# Schematic.net
KiCad netlist of a schematic drawn in Altium Designer
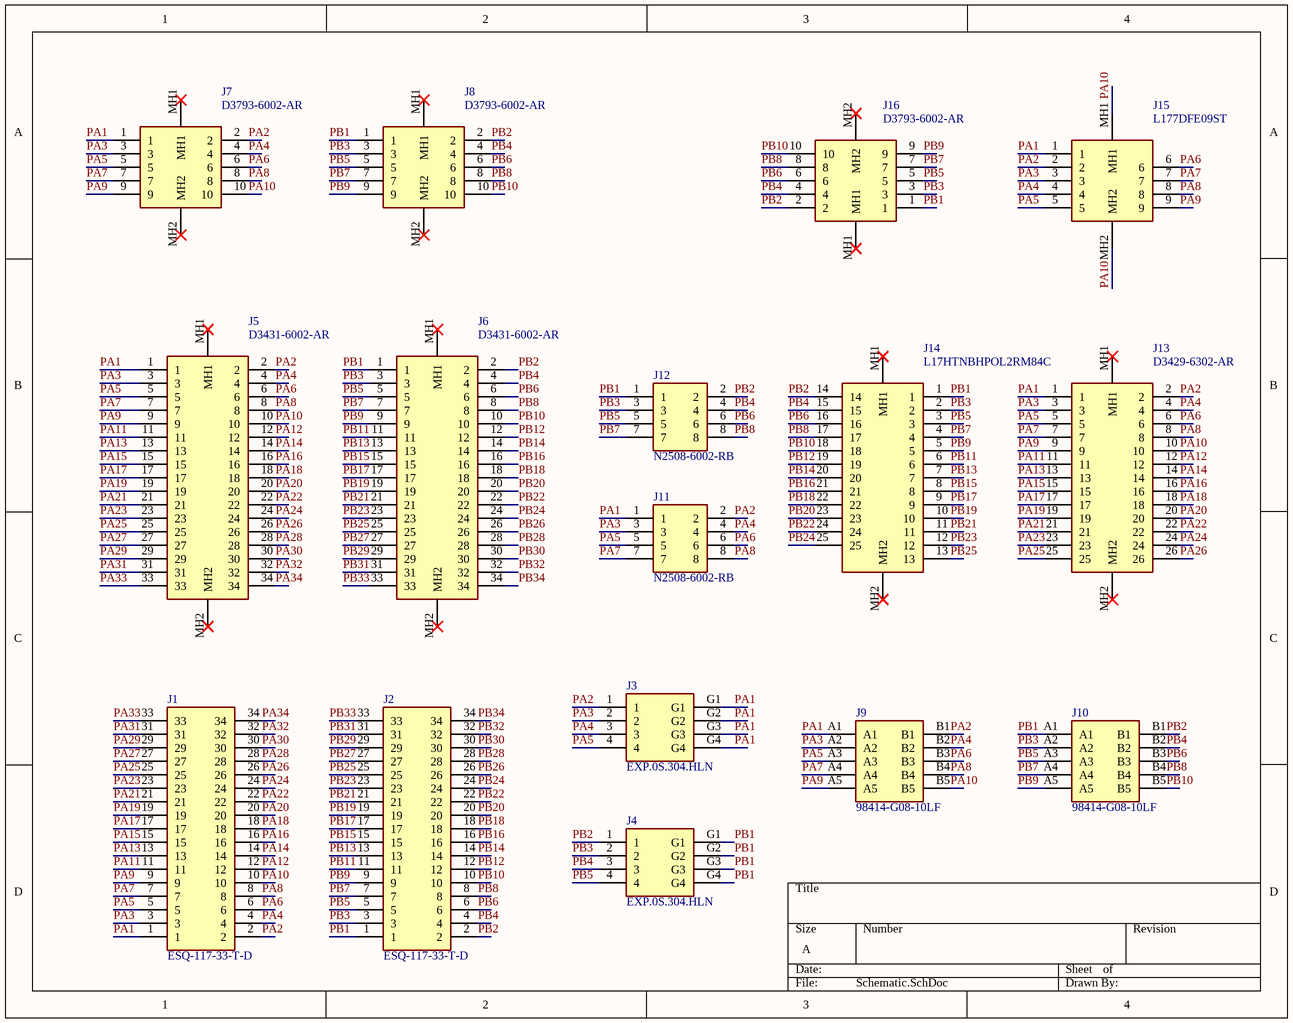
[diagram p0: Schematic.SchDoc]

(export (version "E")
  (design (tool "Eeschema 10.0.6"))
  (components
    (comp (ref "J1")
      (value "ESQ-117-33-T-D")
      (footprint "ESQ-117-Y-X-D")
      (description "Connector")
      (fields
        (field (name "MANUFACTURER_PART_NUMBER") "ESQ-117-44-T-D")
        (field (name "MOUSER PART NUMBER") "200-ESQ11744TD")
      )
      (libsource (lib "Connectors") (part "ESQ-117-33-T-D"))
    )
    (comp (ref "J2")
      (value "ESQ-117-33-T-D")
      (footprint "ESQ-117-Y-X-D")
      (description "Connector")
      (fields
        (field (name "MANUFACTURER_PART_NUMBER") "ESQ-117-44-T-D")
        (field (name "MOUSER PART NUMBER") "200-ESQ11744TD")
      )
      (libsource (lib "Connectors") (part "ESQ-117-33-T-D"))
    )
    (comp (ref "J3")
      (value "EXP.0S.304.HLN")
      (footprint "EXP0S304HLN")
      (description "Connector")
      (fields (field (name "MOUSER PART NUMBER") "736-EXP0S304HLN"))
      (libsource (lib "Connectors") (part "EXP.0S.304.HLN"))
    )
    (comp (ref "J4")
      (value "EXP.0S.304.HLN")
      (footprint "EXP0S304HLN")
      (description "Connector")
      (fields (field (name "MOUSER PART NUMBER") "736-EXP0S304HLN"))
      (libsource (lib "Connectors") (part "EXP.0S.304.HLN"))
    )
    (comp (ref "J5")
      (value "D3431-6002-AR")
      (footprint "D3431-6002-AR")
      (description "Connector")
      (libsource (lib "Connectors") (part "D3431-6002-AR"))
    )
    (comp (ref "J6")
      (value "D3431-6002-AR")
      (footprint "D3431-6002-AR")
      (description "Connector")
      (libsource (lib "Connectors") (part "D3431-6002-AR"))
    )
    (comp (ref "J7")
      (value "D3793-6002-AR")
      (footprint "D3793-6002-AR")
      (description "Connector")
      (libsource (lib "Connectors") (part "D3793-6002-AR"))
    )
    (comp (ref "J8")
      (value "D3793-6002-AR")
      (footprint "D3793-6002-AR")
      (description "Connector")
      (libsource (lib "Connectors") (part "D3793-6002-AR"))
    )
    (comp (ref "J9")
      (value "98414-G08-10LF")
      (footprint "98414G0810LF")
      (description "Connector")
      (fields (field (name "MOUSER PART NUMBER") "649-98414-G08-10LF"))
      (libsource (lib "Connectors") (part "98414-G08-10LF"))
    )
    (comp (ref "J10")
      (value "98414-G08-10LF")
      (footprint "98414G0810LF")
      (description "Connector")
      (fields (field (name "MOUSER PART NUMBER") "649-98414-G08-10LF"))
      (libsource (lib "Connectors") (part "98414-G08-10LF"))
    )
    (comp (ref "J11")
      (value "N2508-6002-RB")
      (footprint "SHDR8W64P254_2X4_1748X859X1004P")
      (description "Connector")
      (fields (field (name "MOUSER PART NUMBER") "517-N2508-6002-RB"))
      (libsource (lib "Connectors") (part "N2508-6002-RB"))
    )
    (comp (ref "J12")
      (value "N2508-6002-RB")
      (footprint "SHDR8W64P254_2X4_1748X859X1004P")
      (description "Connector")
      (fields (field (name "MOUSER PART NUMBER") "517-N2508-6002-RB"))
      (libsource (lib "Connectors") (part "N2508-6002-RB"))
    )
    (comp (ref "J13")
      (value "D3429-6302-AR")
      (footprint "D34296302AR")
      (description "Connector")
      (fields (field (name "MOUSER PART NUMBER") "517-D3429-6302-AR"))
      (libsource (lib "Connectors") (part "D3429-6302-AR"))
    )
    (comp (ref "J14")
      (value "L17HTNBHPOL2RM84C")
      (footprint "L17HTNBHPOL2RM84C")
      (description "Connector")
      (fields (field (name "MOUSER PART NUMBER") "523-17HTNBHPOL2RM84C"))
      (libsource (lib "Connectors") (part "L17HTNBHPOL2RM84C"))
    )
    (comp (ref "J15")
      (value "L177DFE09ST")
      (footprint "L177DFE09ST")
      (description "Connector")
      (libsource (lib "Connectors") (part "L177DFE09ST"))
    )
    (comp (ref "J16")
      (value "D3793-6002-AR")
      (footprint "D3793-6002-AR")
      (description "Connector")
      (libsource (lib "") (part "D3793-6002-AR_1"))
    )
  )
  (nets
    (net (code "1") (name "/PA1") (class "Default")
      (node (ref "J1") (pin "1") (pinfunction "1_1") (pintype "passive"))
      (node (ref "J11") (pin "1") (pinfunction "1_1") (pintype "passive"))
      (node (ref "J13") (pin "1") (pinfunction "1_1") (pintype "passive"))
      (node (ref "J15") (pin "1") (pinfunction "1_1") (pintype "passive"))
      (node (ref "J3") (pin "G1") (pinfunction "G1_G1") (pintype "passive"))
      (node (ref "J3") (pin "G2") (pinfunction "G2_G2") (pintype "passive"))
      (node (ref "J3") (pin "G3") (pinfunction "G3_G3") (pintype "passive"))
      (node (ref "J3") (pin "G4") (pinfunction "G4_G4") (pintype "passive"))
      (node (ref "J5") (pin "1") (pinfunction "1_1") (pintype "passive"))
      (node (ref "J7") (pin "1") (pinfunction "1_1") (pintype "passive"))
      (node (ref "J9") (pin "A1") (pinfunction "A1_A1") (pintype "passive"))
    )
    (net (code "2") (name "/PA2") (class "Default")
      (node (ref "J1") (pin "2") (pinfunction "2_2") (pintype "passive"))
      (node (ref "J11") (pin "2") (pinfunction "2_2") (pintype "passive"))
      (node (ref "J13") (pin "2") (pinfunction "2_2") (pintype "passive"))
      (node (ref "J15") (pin "2") (pinfunction "2_2") (pintype "passive"))
      (node (ref "J3") (pin "1") (pinfunction "1_1") (pintype "passive"))
      (node (ref "J5") (pin "2") (pinfunction "2_2") (pintype "passive"))
      (node (ref "J7") (pin "2") (pinfunction "2_2") (pintype "passive"))
      (node (ref "J9") (pin "B1") (pinfunction "B1_B1") (pintype "passive"))
    )
    (net (code "3") (name "/PA3") (class "Default")
      (node (ref "J1") (pin "3") (pinfunction "3_3") (pintype "passive"))
      (node (ref "J11") (pin "3") (pinfunction "3_3") (pintype "passive"))
      (node (ref "J13") (pin "3") (pinfunction "3_3") (pintype "passive"))
      (node (ref "J15") (pin "3") (pinfunction "3_3") (pintype "passive"))
      (node (ref "J3") (pin "2") (pinfunction "2_2") (pintype "passive"))
      (node (ref "J5") (pin "3") (pinfunction "3_3") (pintype "passive"))
      (node (ref "J7") (pin "3") (pinfunction "3_3") (pintype "passive"))
      (node (ref "J9") (pin "A2") (pinfunction "A2_A2") (pintype "passive"))
    )
    (net (code "4") (name "/PA4") (class "Default")
      (node (ref "J1") (pin "4") (pinfunction "4_4") (pintype "passive"))
      (node (ref "J11") (pin "4") (pinfunction "4_4") (pintype "passive"))
      (node (ref "J13") (pin "4") (pinfunction "4_4") (pintype "passive"))
      (node (ref "J15") (pin "4") (pinfunction "4_4") (pintype "passive"))
      (node (ref "J3") (pin "3") (pinfunction "3_3") (pintype "passive"))
      (node (ref "J5") (pin "4") (pinfunction "4_4") (pintype "passive"))
      (node (ref "J7") (pin "4") (pinfunction "4_4") (pintype "passive"))
      (node (ref "J9") (pin "B2") (pinfunction "B2_B2") (pintype "passive"))
    )
    (net (code "5") (name "/PA5") (class "Default")
      (node (ref "J1") (pin "5") (pinfunction "5_5") (pintype "passive"))
      (node (ref "J11") (pin "5") (pinfunction "5_5") (pintype "passive"))
      (node (ref "J13") (pin "5") (pinfunction "5_5") (pintype "passive"))
      (node (ref "J15") (pin "5") (pinfunction "5_5") (pintype "passive"))
      (node (ref "J3") (pin "4") (pinfunction "4_4") (pintype "passive"))
      (node (ref "J5") (pin "5") (pinfunction "5_5") (pintype "passive"))
      (node (ref "J7") (pin "5") (pinfunction "5_5") (pintype "passive"))
      (node (ref "J9") (pin "A3") (pinfunction "A3_A3") (pintype "passive"))
    )
    (net (code "6") (name "/PA6") (class "Default")
      (node (ref "J1") (pin "6") (pinfunction "6_6") (pintype "passive"))
      (node (ref "J11") (pin "6") (pinfunction "6_6") (pintype "passive"))
      (node (ref "J13") (pin "6") (pinfunction "6_6") (pintype "passive"))
      (node (ref "J15") (pin "6") (pinfunction "6_6") (pintype "passive"))
      (node (ref "J5") (pin "6") (pinfunction "6_6") (pintype "passive"))
      (node (ref "J7") (pin "6") (pinfunction "6_6") (pintype "passive"))
      (node (ref "J9") (pin "B3") (pinfunction "B3_B3") (pintype "passive"))
    )
    (net (code "7") (name "/PA7") (class "Default")
      (node (ref "J1") (pin "7") (pinfunction "7_7") (pintype "passive"))
      (node (ref "J11") (pin "7") (pinfunction "7_7") (pintype "passive"))
      (node (ref "J13") (pin "7") (pinfunction "7_7") (pintype "passive"))
      (node (ref "J15") (pin "7") (pinfunction "7_7") (pintype "passive"))
      (node (ref "J5") (pin "7") (pinfunction "7_7") (pintype "passive"))
      (node (ref "J7") (pin "7") (pinfunction "7_7") (pintype "passive"))
      (node (ref "J9") (pin "A4") (pinfunction "A4_A4") (pintype "passive"))
    )
    (net (code "8") (name "/PA8") (class "Default")
      (node (ref "J1") (pin "8") (pinfunction "8_8") (pintype "passive"))
      (node (ref "J11") (pin "8") (pinfunction "8_8") (pintype "passive"))
      (node (ref "J13") (pin "8") (pinfunction "8_8") (pintype "passive"))
      (node (ref "J15") (pin "8") (pinfunction "8_8") (pintype "passive"))
      (node (ref "J5") (pin "8") (pinfunction "8_8") (pintype "passive"))
      (node (ref "J7") (pin "8") (pinfunction "8_8") (pintype "passive"))
      (node (ref "J9") (pin "B4") (pinfunction "B4_B4") (pintype "passive"))
    )
    (net (code "9") (name "/PA9") (class "Default")
      (node (ref "J1") (pin "9") (pinfunction "9_9") (pintype "passive"))
      (node (ref "J13") (pin "9") (pinfunction "9_9") (pintype "passive"))
      (node (ref "J15") (pin "9") (pinfunction "9_9") (pintype "passive"))
      (node (ref "J5") (pin "9") (pinfunction "9_9") (pintype "passive"))
      (node (ref "J7") (pin "9") (pinfunction "9_9") (pintype "passive"))
      (node (ref "J9") (pin "A5") (pinfunction "A5_A5") (pintype "passive"))
    )
    (net (code "10") (name "/PA10") (class "Default")
      (node (ref "J1") (pin "10") (pinfunction "10_10") (pintype "passive"))
      (node (ref "J13") (pin "10") (pinfunction "10_10") (pintype "passive"))
      (node (ref "J15") (pin "MH1") (pinfunction "MH1_MH1") (pintype "passive"))
      (node (ref "J15") (pin "MH2") (pinfunction "MH2_MH2") (pintype "passive"))
      (node (ref "J5") (pin "10") (pinfunction "10_10") (pintype "passive"))
      (node (ref "J7") (pin "10") (pinfunction "10_10") (pintype "passive"))
      (node (ref "J9") (pin "B5") (pinfunction "B5_B5") (pintype "passive"))
    )
    (net (code "11") (name "/PA11") (class "Default")
      (node (ref "J1") (pin "11") (pinfunction "11_11") (pintype "passive"))
      (node (ref "J13") (pin "11") (pinfunction "11_11") (pintype "passive"))
      (node (ref "J5") (pin "11") (pinfunction "11_11") (pintype "passive"))
    )
    (net (code "12") (name "/PA12") (class "Default")
      (node (ref "J1") (pin "12") (pinfunction "12_12") (pintype "passive"))
      (node (ref "J13") (pin "12") (pinfunction "12_12") (pintype "passive"))
      (node (ref "J5") (pin "12") (pinfunction "12_12") (pintype "passive"))
    )
    (net (code "13") (name "/PA13") (class "Default")
      (node (ref "J1") (pin "13") (pinfunction "13_13") (pintype "passive"))
      (node (ref "J13") (pin "13") (pinfunction "13_13") (pintype "passive"))
      (node (ref "J5") (pin "13") (pinfunction "13_13") (pintype "passive"))
    )
    (net (code "14") (name "/PA14") (class "Default")
      (node (ref "J1") (pin "14") (pinfunction "14_14") (pintype "passive"))
      (node (ref "J13") (pin "14") (pinfunction "14_14") (pintype "passive"))
      (node (ref "J5") (pin "14") (pinfunction "14_14") (pintype "passive"))
    )
    (net (code "15") (name "/PA15") (class "Default")
      (node (ref "J1") (pin "15") (pinfunction "15_15") (pintype "passive"))
      (node (ref "J13") (pin "15") (pinfunction "15_15") (pintype "passive"))
      (node (ref "J5") (pin "15") (pinfunction "15_15") (pintype "passive"))
    )
    (net (code "16") (name "/PA16") (class "Default")
      (node (ref "J1") (pin "16") (pinfunction "16_16") (pintype "passive"))
      (node (ref "J13") (pin "16") (pinfunction "16_16") (pintype "passive"))
      (node (ref "J5") (pin "16") (pinfunction "16_16") (pintype "passive"))
    )
    (net (code "17") (name "/PA17") (class "Default")
      (node (ref "J1") (pin "17") (pinfunction "17_17") (pintype "passive"))
      (node (ref "J13") (pin "17") (pinfunction "17_17") (pintype "passive"))
      (node (ref "J5") (pin "17") (pinfunction "17_17") (pintype "passive"))
    )
    (net (code "18") (name "/PA18") (class "Default")
      (node (ref "J1") (pin "18") (pinfunction "18_18") (pintype "passive"))
      (node (ref "J13") (pin "18") (pinfunction "18_18") (pintype "passive"))
      (node (ref "J5") (pin "18") (pinfunction "18_18") (pintype "passive"))
    )
    (net (code "19") (name "/PA19") (class "Default")
      (node (ref "J1") (pin "19") (pinfunction "19_19") (pintype "passive"))
      (node (ref "J13") (pin "19") (pinfunction "19_19") (pintype "passive"))
      (node (ref "J5") (pin "19") (pinfunction "19_19") (pintype "passive"))
    )
    (net (code "20") (name "/PA20") (class "Default")
      (node (ref "J1") (pin "20") (pinfunction "20_20") (pintype "passive"))
      (node (ref "J13") (pin "20") (pinfunction "20_20") (pintype "passive"))
      (node (ref "J5") (pin "20") (pinfunction "20_20") (pintype "passive"))
    )
    (net (code "21") (name "/PA21") (class "Default")
      (node (ref "J1") (pin "21") (pinfunction "21_21") (pintype "passive"))
      (node (ref "J13") (pin "21") (pinfunction "21_21") (pintype "passive"))
      (node (ref "J5") (pin "21") (pinfunction "21_21") (pintype "passive"))
    )
    (net (code "22") (name "/PA22") (class "Default")
      (node (ref "J1") (pin "22") (pinfunction "22_22") (pintype "passive"))
      (node (ref "J13") (pin "22") (pinfunction "22_22") (pintype "passive"))
      (node (ref "J5") (pin "22") (pinfunction "22_22") (pintype "passive"))
    )
    (net (code "23") (name "/PA23") (class "Default")
      (node (ref "J1") (pin "23") (pinfunction "23_23") (pintype "passive"))
      (node (ref "J13") (pin "23") (pinfunction "23_23") (pintype "passive"))
      (node (ref "J5") (pin "23") (pinfunction "23_23") (pintype "passive"))
    )
    (net (code "24") (name "/PA24") (class "Default")
      (node (ref "J1") (pin "24") (pinfunction "24_24") (pintype "passive"))
      (node (ref "J13") (pin "24") (pinfunction "24_24") (pintype "passive"))
      (node (ref "J5") (pin "24") (pinfunction "24_24") (pintype "passive"))
    )
    (net (code "25") (name "/PA25") (class "Default")
      (node (ref "J1") (pin "25") (pinfunction "25_25") (pintype "passive"))
      (node (ref "J13") (pin "25") (pinfunction "25_25") (pintype "passive"))
      (node (ref "J5") (pin "25") (pinfunction "25_25") (pintype "passive"))
    )
    (net (code "26") (name "/PA26") (class "Default")
      (node (ref "J1") (pin "26") (pinfunction "26_26") (pintype "passive"))
      (node (ref "J13") (pin "26") (pinfunction "26_26") (pintype "passive"))
      (node (ref "J5") (pin "26") (pinfunction "26_26") (pintype "passive"))
    )
    (net (code "27") (name "/PA27") (class "Default")
      (node (ref "J1") (pin "27") (pinfunction "27_27") (pintype "passive"))
      (node (ref "J5") (pin "27") (pinfunction "27_27") (pintype "passive"))
    )
    (net (code "28") (name "/PA28") (class "Default")
      (node (ref "J1") (pin "28") (pinfunction "28_28") (pintype "passive"))
      (node (ref "J5") (pin "28") (pinfunction "28_28") (pintype "passive"))
    )
    (net (code "29") (name "/PA29") (class "Default")
      (node (ref "J1") (pin "29") (pinfunction "29_29") (pintype "passive"))
      (node (ref "J5") (pin "29") (pinfunction "29_29") (pintype "passive"))
    )
    (net (code "30") (name "/PA30") (class "Default")
      (node (ref "J1") (pin "30") (pinfunction "30_30") (pintype "passive"))
      (node (ref "J5") (pin "30") (pinfunction "30_30") (pintype "passive"))
    )
    (net (code "31") (name "/PA31") (class "Default")
      (node (ref "J1") (pin "31") (pinfunction "31_31") (pintype "passive"))
      (node (ref "J5") (pin "31") (pinfunction "31_31") (pintype "passive"))
    )
    (net (code "32") (name "/PA32") (class "Default")
      (node (ref "J1") (pin "32") (pinfunction "32_32") (pintype "passive"))
      (node (ref "J5") (pin "32") (pinfunction "32_32") (pintype "passive"))
    )
    (net (code "33") (name "/PA33") (class "Default")
      (node (ref "J1") (pin "33") (pinfunction "33_33") (pintype "passive"))
      (node (ref "J5") (pin "33") (pinfunction "33_33") (pintype "passive"))
    )
    (net (code "34") (name "/PA34") (class "Default")
      (node (ref "J1") (pin "34") (pinfunction "34_34") (pintype "passive"))
      (node (ref "J5") (pin "34") (pinfunction "34_34") (pintype "passive"))
    )
    (net (code "35") (name "/PB1") (class "Default")
      (node (ref "J10") (pin "A1") (pinfunction "A1_A1") (pintype "passive"))
      (node (ref "J12") (pin "1") (pinfunction "1_1") (pintype "passive"))
      (node (ref "J14") (pin "1") (pinfunction "1_1") (pintype "passive"))
      (node (ref "J16") (pin "1") (pinfunction "1_1") (pintype "passive"))
      (node (ref "J2") (pin "1") (pinfunction "1_1") (pintype "passive"))
      (node (ref "J4") (pin "G1") (pinfunction "G1_G1") (pintype "passive"))
      (node (ref "J4") (pin "G2") (pinfunction "G2_G2") (pintype "passive"))
      (node (ref "J4") (pin "G3") (pinfunction "G3_G3") (pintype "passive"))
      (node (ref "J4") (pin "G4") (pinfunction "G4_G4") (pintype "passive"))
      (node (ref "J6") (pin "1") (pinfunction "1_1") (pintype "passive"))
      (node (ref "J8") (pin "1") (pinfunction "1_1") (pintype "passive"))
    )
    (net (code "36") (name "/PB2") (class "Default")
      (node (ref "J10") (pin "B1") (pinfunction "B1_B1") (pintype "passive"))
      (node (ref "J12") (pin "2") (pinfunction "2_2") (pintype "passive"))
      (node (ref "J14") (pin "14") (pinfunction "14_14") (pintype "passive"))
      (node (ref "J16") (pin "2") (pinfunction "2_2") (pintype "passive"))
      (node (ref "J2") (pin "2") (pinfunction "2_2") (pintype "passive"))
      (node (ref "J4") (pin "1") (pinfunction "1_1") (pintype "passive"))
      (node (ref "J6") (pin "2") (pinfunction "2_2") (pintype "passive"))
      (node (ref "J8") (pin "2") (pinfunction "2_2") (pintype "passive"))
    )
    (net (code "37") (name "/PB3") (class "Default")
      (node (ref "J10") (pin "A2") (pinfunction "A2_A2") (pintype "passive"))
      (node (ref "J12") (pin "3") (pinfunction "3_3") (pintype "passive"))
      (node (ref "J14") (pin "2") (pinfunction "2_2") (pintype "passive"))
      (node (ref "J16") (pin "3") (pinfunction "3_3") (pintype "passive"))
      (node (ref "J2") (pin "3") (pinfunction "3_3") (pintype "passive"))
      (node (ref "J4") (pin "2") (pinfunction "2_2") (pintype "passive"))
      (node (ref "J6") (pin "3") (pinfunction "3_3") (pintype "passive"))
      (node (ref "J8") (pin "3") (pinfunction "3_3") (pintype "passive"))
    )
    (net (code "38") (name "/PB4") (class "Default")
      (node (ref "J10") (pin "B2") (pinfunction "B2_B2") (pintype "passive"))
      (node (ref "J12") (pin "4") (pinfunction "4_4") (pintype "passive"))
      (node (ref "J14") (pin "15") (pinfunction "15_15") (pintype "passive"))
      (node (ref "J16") (pin "4") (pinfunction "4_4") (pintype "passive"))
      (node (ref "J2") (pin "4") (pinfunction "4_4") (pintype "passive"))
      (node (ref "J4") (pin "3") (pinfunction "3_3") (pintype "passive"))
      (node (ref "J6") (pin "4") (pinfunction "4_4") (pintype "passive"))
      (node (ref "J8") (pin "4") (pinfunction "4_4") (pintype "passive"))
    )
    (net (code "39") (name "/PB5") (class "Default")
      (node (ref "J10") (pin "A3") (pinfunction "A3_A3") (pintype "passive"))
      (node (ref "J12") (pin "5") (pinfunction "5_5") (pintype "passive"))
      (node (ref "J14") (pin "3") (pinfunction "3_3") (pintype "passive"))
      (node (ref "J16") (pin "5") (pinfunction "5_5") (pintype "passive"))
      (node (ref "J2") (pin "5") (pinfunction "5_5") (pintype "passive"))
      (node (ref "J4") (pin "4") (pinfunction "4_4") (pintype "passive"))
      (node (ref "J6") (pin "5") (pinfunction "5_5") (pintype "passive"))
      (node (ref "J8") (pin "5") (pinfunction "5_5") (pintype "passive"))
    )
    (net (code "40") (name "/PB6") (class "Default")
      (node (ref "J10") (pin "B3") (pinfunction "B3_B3") (pintype "passive"))
      (node (ref "J12") (pin "6") (pinfunction "6_6") (pintype "passive"))
      (node (ref "J14") (pin "16") (pinfunction "16_16") (pintype "passive"))
      (node (ref "J16") (pin "6") (pinfunction "6_6") (pintype "passive"))
      (node (ref "J2") (pin "6") (pinfunction "6_6") (pintype "passive"))
      (node (ref "J6") (pin "6") (pinfunction "6_6") (pintype "passive"))
      (node (ref "J8") (pin "6") (pinfunction "6_6") (pintype "passive"))
    )
    (net (code "41") (name "/PB7") (class "Default")
      (node (ref "J10") (pin "A4") (pinfunction "A4_A4") (pintype "passive"))
      (node (ref "J12") (pin "7") (pinfunction "7_7") (pintype "passive"))
      (node (ref "J14") (pin "4") (pinfunction "4_4") (pintype "passive"))
      (node (ref "J16") (pin "7") (pinfunction "7_7") (pintype "passive"))
      (node (ref "J2") (pin "7") (pinfunction "7_7") (pintype "passive"))
      (node (ref "J6") (pin "7") (pinfunction "7_7") (pintype "passive"))
      (node (ref "J8") (pin "7") (pinfunction "7_7") (pintype "passive"))
    )
    (net (code "42") (name "/PB8") (class "Default")
      (node (ref "J10") (pin "B4") (pinfunction "B4_B4") (pintype "passive"))
      (node (ref "J12") (pin "8") (pinfunction "8_8") (pintype "passive"))
      (node (ref "J14") (pin "17") (pinfunction "17_17") (pintype "passive"))
      (node (ref "J16") (pin "8") (pinfunction "8_8") (pintype "passive"))
      (node (ref "J2") (pin "8") (pinfunction "8_8") (pintype "passive"))
      (node (ref "J6") (pin "8") (pinfunction "8_8") (pintype "passive"))
      (node (ref "J8") (pin "8") (pinfunction "8_8") (pintype "passive"))
    )
    (net (code "43") (name "/PB9") (class "Default")
      (node (ref "J10") (pin "A5") (pinfunction "A5_A5") (pintype "passive"))
      (node (ref "J14") (pin "5") (pinfunction "5_5") (pintype "passive"))
      (node (ref "J16") (pin "9") (pinfunction "9_9") (pintype "passive"))
      (node (ref "J2") (pin "9") (pinfunction "9_9") (pintype "passive"))
      (node (ref "J6") (pin "9") (pinfunction "9_9") (pintype "passive"))
      (node (ref "J8") (pin "9") (pinfunction "9_9") (pintype "passive"))
    )
    (net (code "44") (name "/PB10") (class "Default")
      (node (ref "J10") (pin "B5") (pinfunction "B5_B5") (pintype "passive"))
      (node (ref "J14") (pin "18") (pinfunction "18_18") (pintype "passive"))
      (node (ref "J16") (pin "10") (pinfunction "10_10") (pintype "passive"))
      (node (ref "J2") (pin "10") (pinfunction "10_10") (pintype "passive"))
      (node (ref "J6") (pin "10") (pinfunction "10_10") (pintype "passive"))
      (node (ref "J8") (pin "10") (pinfunction "10_10") (pintype "passive"))
    )
    (net (code "45") (name "/PB11") (class "Default")
      (node (ref "J14") (pin "6") (pinfunction "6_6") (pintype "passive"))
      (node (ref "J2") (pin "11") (pinfunction "11_11") (pintype "passive"))
      (node (ref "J6") (pin "11") (pinfunction "11_11") (pintype "passive"))
    )
    (net (code "46") (name "/PB12") (class "Default")
      (node (ref "J14") (pin "19") (pinfunction "19_19") (pintype "passive"))
      (node (ref "J2") (pin "12") (pinfunction "12_12") (pintype "passive"))
      (node (ref "J6") (pin "12") (pinfunction "12_12") (pintype "passive"))
    )
    (net (code "47") (name "/PB13") (class "Default")
      (node (ref "J14") (pin "7") (pinfunction "7_7") (pintype "passive"))
      (node (ref "J2") (pin "13") (pinfunction "13_13") (pintype "passive"))
      (node (ref "J6") (pin "13") (pinfunction "13_13") (pintype "passive"))
    )
    (net (code "48") (name "/PB14") (class "Default")
      (node (ref "J14") (pin "20") (pinfunction "20_20") (pintype "passive"))
      (node (ref "J2") (pin "14") (pinfunction "14_14") (pintype "passive"))
      (node (ref "J6") (pin "14") (pinfunction "14_14") (pintype "passive"))
    )
    (net (code "49") (name "/PB15") (class "Default")
      (node (ref "J14") (pin "8") (pinfunction "8_8") (pintype "passive"))
      (node (ref "J2") (pin "15") (pinfunction "15_15") (pintype "passive"))
      (node (ref "J6") (pin "15") (pinfunction "15_15") (pintype "passive"))
    )
    (net (code "50") (name "/PB16") (class "Default")
      (node (ref "J14") (pin "21") (pinfunction "21_21") (pintype "passive"))
      (node (ref "J2") (pin "16") (pinfunction "16_16") (pintype "passive"))
      (node (ref "J6") (pin "16") (pinfunction "16_16") (pintype "passive"))
    )
    (net (code "51") (name "/PB17") (class "Default")
      (node (ref "J14") (pin "9") (pinfunction "9_9") (pintype "passive"))
      (node (ref "J2") (pin "17") (pinfunction "17_17") (pintype "passive"))
      (node (ref "J6") (pin "17") (pinfunction "17_17") (pintype "passive"))
    )
    (net (code "52") (name "/PB18") (class "Default")
      (node (ref "J14") (pin "22") (pinfunction "22_22") (pintype "passive"))
      (node (ref "J2") (pin "18") (pinfunction "18_18") (pintype "passive"))
      (node (ref "J6") (pin "18") (pinfunction "18_18") (pintype "passive"))
    )
    (net (code "53") (name "/PB19") (class "Default")
      (node (ref "J14") (pin "10") (pinfunction "10_10") (pintype "passive"))
      (node (ref "J2") (pin "19") (pinfunction "19_19") (pintype "passive"))
      (node (ref "J6") (pin "19") (pinfunction "19_19") (pintype "passive"))
    )
    (net (code "54") (name "/PB20") (class "Default")
      (node (ref "J14") (pin "23") (pinfunction "23_23") (pintype "passive"))
      (node (ref "J2") (pin "20") (pinfunction "20_20") (pintype "passive"))
      (node (ref "J6") (pin "20") (pinfunction "20_20") (pintype "passive"))
    )
    (net (code "55") (name "/PB21") (class "Default")
      (node (ref "J14") (pin "11") (pinfunction "11_11") (pintype "passive"))
      (node (ref "J2") (pin "21") (pinfunction "21_21") (pintype "passive"))
      (node (ref "J6") (pin "21") (pinfunction "21_21") (pintype "passive"))
    )
    (net (code "56") (name "/PB22") (class "Default")
      (node (ref "J14") (pin "24") (pinfunction "24_24") (pintype "passive"))
      (node (ref "J2") (pin "22") (pinfunction "22_22") (pintype "passive"))
      (node (ref "J6") (pin "22") (pinfunction "22_22") (pintype "passive"))
    )
    (net (code "57") (name "/PB23") (class "Default")
      (node (ref "J14") (pin "12") (pinfunction "12_12") (pintype "passive"))
      (node (ref "J2") (pin "23") (pinfunction "23_23") (pintype "passive"))
      (node (ref "J6") (pin "23") (pinfunction "23_23") (pintype "passive"))
    )
    (net (code "58") (name "/PB24") (class "Default")
      (node (ref "J14") (pin "25") (pinfunction "25_25") (pintype "passive"))
      (node (ref "J2") (pin "24") (pinfunction "24_24") (pintype "passive"))
      (node (ref "J6") (pin "24") (pinfunction "24_24") (pintype "passive"))
    )
    (net (code "59") (name "/PB25") (class "Default")
      (node (ref "J14") (pin "13") (pinfunction "13_13") (pintype "passive"))
      (node (ref "J2") (pin "25") (pinfunction "25_25") (pintype "passive"))
      (node (ref "J6") (pin "25") (pinfunction "25_25") (pintype "passive"))
    )
    (net (code "60") (name "/PB26") (class "Default")
      (node (ref "J2") (pin "26") (pinfunction "26_26") (pintype "passive"))
      (node (ref "J6") (pin "26") (pinfunction "26_26") (pintype "passive"))
    )
    (net (code "61") (name "/PB27") (class "Default")
      (node (ref "J2") (pin "27") (pinfunction "27_27") (pintype "passive"))
      (node (ref "J6") (pin "27") (pinfunction "27_27") (pintype "passive"))
    )
    (net (code "62") (name "/PB28") (class "Default")
      (node (ref "J2") (pin "28") (pinfunction "28_28") (pintype "passive"))
      (node (ref "J6") (pin "28") (pinfunction "28_28") (pintype "passive"))
    )
    (net (code "63") (name "/PB29") (class "Default")
      (node (ref "J2") (pin "29") (pinfunction "29_29") (pintype "passive"))
      (node (ref "J6") (pin "29") (pinfunction "29_29") (pintype "passive"))
    )
    (net (code "64") (name "/PB30") (class "Default")
      (node (ref "J2") (pin "30") (pinfunction "30_30") (pintype "passive"))
      (node (ref "J6") (pin "30") (pinfunction "30_30") (pintype "passive"))
    )
    (net (code "65") (name "/PB31") (class "Default")
      (node (ref "J2") (pin "31") (pinfunction "31_31") (pintype "passive"))
      (node (ref "J6") (pin "31") (pinfunction "31_31") (pintype "passive"))
    )
    (net (code "66") (name "/PB32") (class "Default")
      (node (ref "J2") (pin "32") (pinfunction "32_32") (pintype "passive"))
      (node (ref "J6") (pin "32") (pinfunction "32_32") (pintype "passive"))
    )
    (net (code "67") (name "/PB33") (class "Default")
      (node (ref "J2") (pin "33") (pinfunction "33_33") (pintype "passive"))
      (node (ref "J6") (pin "33") (pinfunction "33_33") (pintype "passive"))
    )
    (net (code "68") (name "/PB34") (class "Default")
      (node (ref "J2") (pin "34") (pinfunction "34_34") (pintype "passive"))
      (node (ref "J6") (pin "34") (pinfunction "34_34") (pintype "passive"))
    )
    (net (code "69") (name "unconnected-(J5-PadMH1)") (class "Default")
      (node (ref "J5") (pin "MH1") (pinfunction "MH1_MH1") (pintype "passive+no_connect"))
    )
    (net (code "70") (name "unconnected-(J5-PadMH2)") (class "Default")
      (node (ref "J5") (pin "MH2") (pinfunction "MH2_MH2") (pintype "passive+no_connect"))
    )
    (net (code "71") (name "unconnected-(J6-PadMH1)") (class "Default")
      (node (ref "J6") (pin "MH1") (pinfunction "MH1_MH1") (pintype "passive+no_connect"))
    )
    (net (code "72") (name "unconnected-(J6-PadMH2)") (class "Default")
      (node (ref "J6") (pin "MH2") (pinfunction "MH2_MH2") (pintype "passive+no_connect"))
    )
    (net (code "73") (name "unconnected-(J7-PadMH1)") (class "Default")
      (node (ref "J7") (pin "MH1") (pinfunction "MH1_MH1") (pintype "passive+no_connect"))
    )
    (net (code "74") (name "unconnected-(J7-PadMH2)") (class "Default")
      (node (ref "J7") (pin "MH2") (pinfunction "MH2_MH2") (pintype "passive+no_connect"))
    )
    (net (code "75") (name "unconnected-(J8-PadMH1)") (class "Default")
      (node (ref "J8") (pin "MH1") (pinfunction "MH1_MH1") (pintype "passive+no_connect"))
    )
    (net (code "76") (name "unconnected-(J8-PadMH2)") (class "Default")
      (node (ref "J8") (pin "MH2") (pinfunction "MH2_MH2") (pintype "passive+no_connect"))
    )
    (net (code "77") (name "unconnected-(J13-PadMH1)") (class "Default")
      (node (ref "J13") (pin "MH1") (pinfunction "MH1_MH1") (pintype "passive+no_connect"))
    )
    (net (code "78") (name "unconnected-(J13-PadMH2)") (class "Default")
      (node (ref "J13") (pin "MH2") (pinfunction "MH2_MH2") (pintype "passive+no_connect"))
    )
    (net (code "79") (name "unconnected-(J14-PadMH1)") (class "Default")
      (node (ref "J14") (pin "MH1") (pinfunction "MH1_MH1") (pintype "passive+no_connect"))
    )
    (net (code "80") (name "unconnected-(J14-PadMH2)") (class "Default")
      (node (ref "J14") (pin "MH2") (pinfunction "MH2_MH2") (pintype "passive+no_connect"))
    )
    (net (code "81") (name "unconnected-(J16-PadMH1)") (class "Default")
      (node (ref "J16") (pin "MH1") (pinfunction "MH1_MH1") (pintype "passive+no_connect"))
    )
    (net (code "82") (name "unconnected-(J16-PadMH2)") (class "Default")
      (node (ref "J16") (pin "MH2") (pinfunction "MH2_MH2") (pintype "passive+no_connect"))
    )
  )
)
